# ME_433_Final.net
KiCad netlist of a schematic drawn in EAGLE
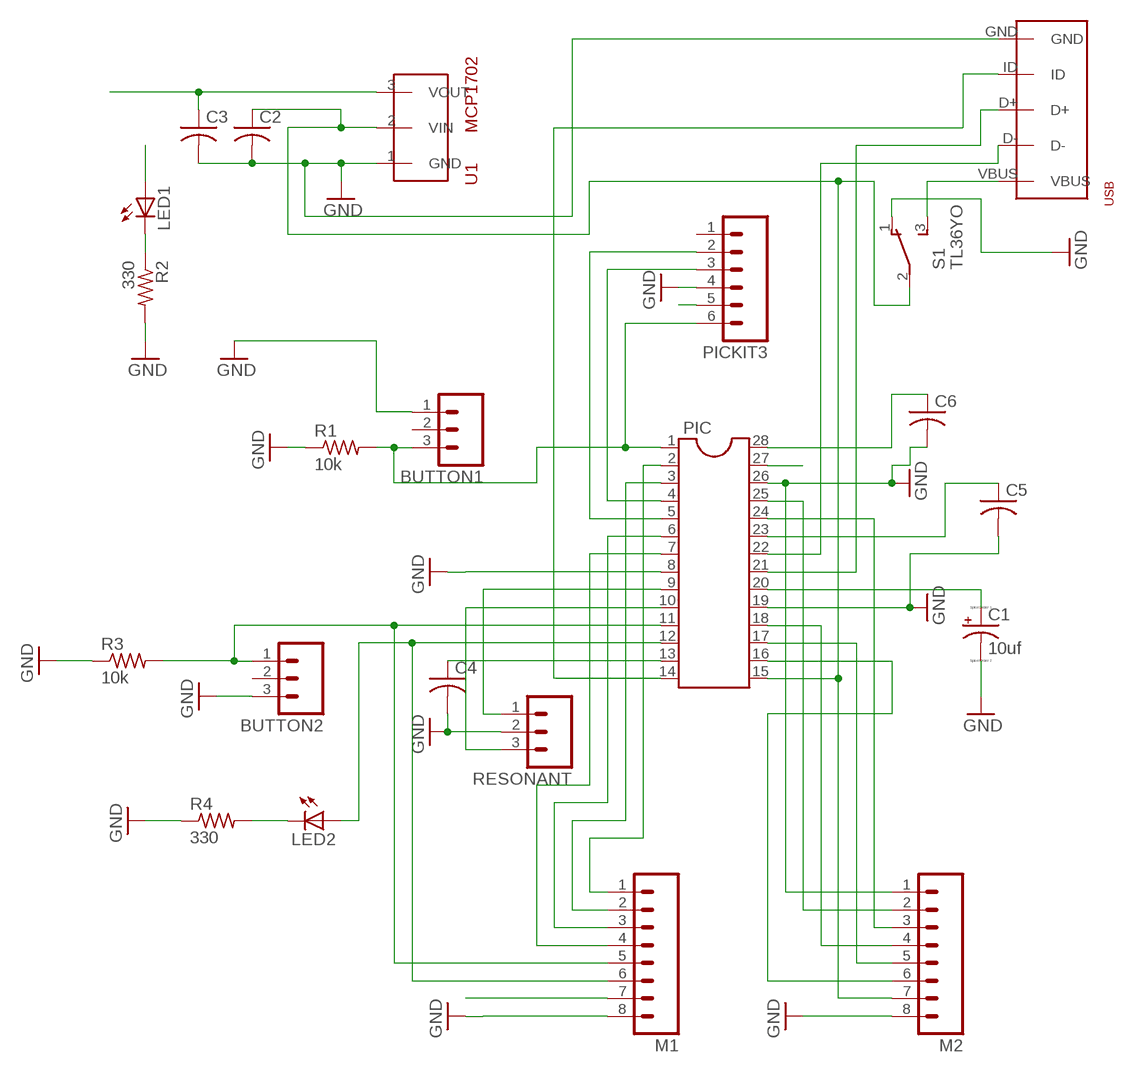
[diagram p0: schematic, sheet 1]

(export (version "E")
  (design (tool "Eeschema 10.0.6"))
  (components
    (comp (ref "BUTTON1")
      (value "M03PTH")
      (footprint "eagle-import:1X03")
      (libsource (lib "eagle-import") (part "M03PTH"))
    )
    (comp (ref "BUTTON2")
      (value "M03PTH")
      (footprint "eagle-import:1X03")
      (libsource (lib "eagle-import") (part "M03PTH"))
    )
    (comp (ref "C1")
      (value "10uf")
      (footprint "eagle-import:E5-10,5")
      (libsource (lib "eagle-import") (part "CPOL-USE5-10.5"))
    )
    (comp (ref "C2")
      (value "C-US025-025X050")
      (footprint "eagle-import:C025-025X050")
      (libsource (lib "eagle-import") (part "C-US025-025X050"))
    )
    (comp (ref "C3")
      (value "C-US025-025X050")
      (footprint "eagle-import:C025-025X050")
      (libsource (lib "eagle-import") (part "C-US025-025X050"))
    )
    (comp (ref "C4")
      (value "C-US025-025X050")
      (footprint "eagle-import:C025-025X050")
      (libsource (lib "eagle-import") (part "C-US025-025X050"))
    )
    (comp (ref "C5")
      (value "C-US025-025X050")
      (footprint "eagle-import:C025-025X050")
      (libsource (lib "eagle-import") (part "C-US025-025X050"))
    )
    (comp (ref "C6")
      (value "C-US025-025X050")
      (footprint "eagle-import:C025-025X050")
      (libsource (lib "eagle-import") (part "C-US025-025X050"))
    )
    (comp (ref "LED1")
      (value "LED3MM")
      (footprint "eagle-import:LED3MM")
      (libsource (lib "eagle-import") (part "LED3MM"))
    )
    (comp (ref "LED2")
      (value "LED3MM")
      (footprint "eagle-import:LED3MM")
      (libsource (lib "eagle-import") (part "LED3MM"))
    )
    (comp (ref "M1")
      (value "M08SILK_FEMALE_PTH")
      (footprint "eagle-import:1X08")
      (libsource (lib "eagle-import") (part "M08SILK_FEMALE_PTH"))
    )
    (comp (ref "M2")
      (value "M08SILK_FEMALE_PTH")
      (footprint "eagle-import:1X08")
      (libsource (lib "eagle-import") (part "M08SILK_FEMALE_PTH"))
    )
    (comp (ref "PIC")
      (value "DIL28-3")
      (footprint "eagle-import:DIL28-3")
      (libsource (lib "eagle-import") (part "DIL28-3"))
    )
    (comp (ref "PICKIT3")
      (value "M06SILK_FEMALE_PTH")
      (footprint "eagle-import:1X06")
      (libsource (lib "eagle-import") (part "M06SILK_FEMALE_PTH"))
    )
    (comp (ref "R1")
      (value "10k")
      (footprint "eagle-import:0309_12")
      (libsource (lib "eagle-import") (part "R-US_0309/12"))
    )
    (comp (ref "R2")
      (value "330")
      (footprint "eagle-import:0309_12")
      (libsource (lib "eagle-import") (part "R-US_0309/12"))
    )
    (comp (ref "R3")
      (value "10k")
      (footprint "eagle-import:0309_12")
      (libsource (lib "eagle-import") (part "R-US_0309/12"))
    )
    (comp (ref "R4")
      (value "330")
      (footprint "eagle-import:0309_12")
      (libsource (lib "eagle-import") (part "R-US_0309/12"))
    )
    (comp (ref "RESONANT")
      (value "M03PTH")
      (footprint "eagle-import:1X03")
      (libsource (lib "eagle-import") (part "M03PTH"))
    )
    (comp (ref "S1")
      (value "TL36YO")
      (footprint "eagle-import:TL3XYO")
      (libsource (lib "eagle-import") (part "TL36YO"))
    )
    (comp (ref "U$1")
      (value "MCP1702TO92")
      (footprint "eagle-import:TO92")
      (libsource (lib "eagle-import") (part "MCP1702TO92"))
    )
    (comp (ref "U$2")
      (value "USB_ME")
      (footprint "eagle-import:USB-MB-H")
      (libsource (lib "eagle-import") (part "USB_ME"))
    )
  )
  (nets
    (net (code "1") (name "/3.3V") (class "Default")
      (node (ref "C3") (pin "1") (pinfunction "1_1") (pintype "passive"))
      (node (ref "C4") (pin "1") (pinfunction "1_1") (pintype "passive"))
      (node (ref "C5") (pin "1") (pinfunction "1_1") (pintype "passive"))
      (node (ref "C6") (pin "1") (pinfunction "1_1") (pintype "passive"))
      (node (ref "LED1") (pin "A") (pinfunction "A_A") (pintype "passive"))
      (node (ref "M1") (pin "7") (pinfunction "7_7") (pintype "passive"))
      (node (ref "PIC") (pin "13") (pinfunction "13_13") (pintype "passive"))
      (node (ref "PIC") (pin "23") (pinfunction "23_23") (pintype "passive"))
      (node (ref "PIC") (pin "28") (pinfunction "28_28") (pintype "passive"))
      (node (ref "PICKIT3") (pin "5") (pinfunction "5_5") (pintype "passive"))
      (node (ref "U$1") (pin "3") (pinfunction "VOUT_3") (pintype "bidirectional"))
    )
    (net (code "2") (name "GND") (class "Default")
      (node (ref "BUTTON1") (pin "1") (pinfunction "1_1") (pintype "passive"))
      (node (ref "BUTTON2") (pin "3") (pinfunction "3_3") (pintype "passive"))
      (node (ref "C1") (pin "-") (pinfunction "-_-") (pintype "passive"))
      (node (ref "C2") (pin "2") (pinfunction "2_2") (pintype "passive"))
      (node (ref "C3") (pin "2") (pinfunction "2_2") (pintype "passive"))
      (node (ref "C4") (pin "2") (pinfunction "2_2") (pintype "passive"))
      (node (ref "C5") (pin "2") (pinfunction "2_2") (pintype "passive"))
      (node (ref "C6") (pin "2") (pinfunction "2_2") (pintype "passive"))
      (node (ref "M1") (pin "8") (pinfunction "8_8") (pintype "passive"))
      (node (ref "M2") (pin "1") (pinfunction "1_1") (pintype "passive"))
      (node (ref "M2") (pin "8") (pinfunction "8_8") (pintype "passive"))
      (node (ref "PIC") (pin "19") (pinfunction "19_19") (pintype "passive"))
      (node (ref "PIC") (pin "26") (pinfunction "26_26") (pintype "passive"))
      (node (ref "PIC") (pin "8") (pinfunction "8_8") (pintype "passive"))
      (node (ref "PICKIT3") (pin "4") (pinfunction "4_4") (pintype "passive"))
      (node (ref "R1") (pin "1") (pinfunction "1_1") (pintype "passive"))
      (node (ref "R2") (pin "2") (pinfunction "2_2") (pintype "passive"))
      (node (ref "R3") (pin "1") (pinfunction "1_1") (pintype "passive"))
      (node (ref "R4") (pin "1") (pinfunction "1_1") (pintype "passive"))
      (node (ref "RESONANT") (pin "2") (pinfunction "2_2") (pintype "passive"))
      (node (ref "S1") (pin "1") (pinfunction "O_1") (pintype "passive"))
      (node (ref "U$1") (pin "1") (pinfunction "GND_1") (pintype "bidirectional"))
      (node (ref "U$2") (pin "GND") (pinfunction "GND_GND") (pintype "bidirectional"))
    )
    (net (code "3") (name "Net-(BUTTON1-Pad3)") (class "Default")
      (node (ref "BUTTON1") (pin "3") (pinfunction "3_3") (pintype "passive"))
      (node (ref "PIC") (pin "1") (pinfunction "1_1") (pintype "passive"))
      (node (ref "PICKIT3") (pin "6") (pinfunction "6_6") (pintype "passive"))
      (node (ref "R1") (pin "2") (pinfunction "2_2") (pintype "passive"))
    )
    (net (code "4") (name "Net-(BUTTON2-Pad1)") (class "Default")
      (node (ref "BUTTON2") (pin "1") (pinfunction "1_1") (pintype "passive"))
      (node (ref "M1") (pin "5") (pinfunction "5_5") (pintype "passive"))
      (node (ref "PIC") (pin "11") (pinfunction "11_11") (pintype "passive"))
      (node (ref "R3") (pin "2") (pinfunction "2_2") (pintype "passive"))
    )
    (net (code "5") (name "Net-(C1-Pad+)") (class "Default")
      (node (ref "C1") (pin "+") (pinfunction "+_+") (pintype "passive"))
      (node (ref "PIC") (pin "20") (pinfunction "20_20") (pintype "passive"))
    )
    (net (code "6") (name "Net-(LED1-C)") (class "Default")
      (node (ref "LED1") (pin "K") (pinfunction "C_K") (pintype "passive"))
      (node (ref "R2") (pin "1") (pinfunction "1_1") (pintype "passive"))
    )
    (net (code "7") (name "Net-(LED2-C)") (class "Default")
      (node (ref "LED2") (pin "K") (pinfunction "C_K") (pintype "passive"))
      (node (ref "R4") (pin "2") (pinfunction "2_2") (pintype "passive"))
    )
    (net (code "8") (name "Net-(LED2-PadA)") (class "Default")
      (node (ref "LED2") (pin "A") (pinfunction "A_A") (pintype "passive"))
      (node (ref "M1") (pin "6") (pinfunction "6_6") (pintype "passive"))
      (node (ref "PIC") (pin "12") (pinfunction "12_12") (pintype "passive"))
    )
    (net (code "9") (name "Net-(M1-Pad1)") (class "Default")
      (node (ref "M1") (pin "1") (pinfunction "1_1") (pintype "passive"))
      (node (ref "PIC") (pin "2") (pinfunction "2_2") (pintype "passive"))
    )
    (net (code "10") (name "Net-(M1-Pad2)") (class "Default")
      (node (ref "M1") (pin "2") (pinfunction "2_2") (pintype "passive"))
      (node (ref "PIC") (pin "3") (pinfunction "3_3") (pintype "passive"))
    )
    (net (code "11") (name "Net-(M1-Pad3)") (class "Default")
      (node (ref "M1") (pin "3") (pinfunction "3_3") (pintype "passive"))
      (node (ref "PIC") (pin "6") (pinfunction "6_6") (pintype "passive"))
    )
    (net (code "12") (name "Net-(M1-Pad4)") (class "Default")
      (node (ref "M1") (pin "4") (pinfunction "4_4") (pintype "passive"))
      (node (ref "PIC") (pin "7") (pinfunction "7_7") (pintype "passive"))
    )
    (net (code "13") (name "Net-(M2-Pad2)") (class "Default")
      (node (ref "M2") (pin "2") (pinfunction "2_2") (pintype "passive"))
      (node (ref "PIC") (pin "25") (pinfunction "25_25") (pintype "passive"))
    )
    (net (code "14") (name "Net-(M2-Pad3)") (class "Default")
      (node (ref "M2") (pin "3") (pinfunction "3_3") (pintype "passive"))
      (node (ref "PIC") (pin "24") (pinfunction "24_24") (pintype "passive"))
    )
    (net (code "15") (name "Net-(M2-Pad4)") (class "Default")
      (node (ref "M2") (pin "4") (pinfunction "4_4") (pintype "passive"))
      (node (ref "PIC") (pin "18") (pinfunction "18_18") (pintype "passive"))
    )
    (net (code "16") (name "Net-(M2-Pad5)") (class "Default")
      (node (ref "M2") (pin "5") (pinfunction "5_5") (pintype "passive"))
      (node (ref "PIC") (pin "17") (pinfunction "17_17") (pintype "passive"))
    )
    (net (code "17") (name "Net-(M2-Pad6)") (class "Default")
      (node (ref "M2") (pin "6") (pinfunction "6_6") (pintype "passive"))
      (node (ref "PIC") (pin "16") (pinfunction "16_16") (pintype "passive"))
    )
    (net (code "18") (name "Net-(PIC-Pad4)") (class "Default")
      (node (ref "PIC") (pin "4") (pinfunction "4_4") (pintype "passive"))
      (node (ref "PICKIT3") (pin "3") (pinfunction "3_3") (pintype "passive"))
    )
    (net (code "19") (name "Net-(PIC-Pad5)") (class "Default")
      (node (ref "PIC") (pin "5") (pinfunction "5_5") (pintype "passive"))
      (node (ref "PICKIT3") (pin "2") (pinfunction "2_2") (pintype "passive"))
    )
    (net (code "20") (name "Net-(PIC-Pad9)") (class "Default")
      (node (ref "PIC") (pin "9") (pinfunction "9_9") (pintype "passive"))
      (node (ref "RESONANT") (pin "1") (pinfunction "1_1") (pintype "passive"))
    )
    (net (code "21") (name "Net-(PIC-Pad10)") (class "Default")
      (node (ref "PIC") (pin "10") (pinfunction "10_10") (pintype "passive"))
      (node (ref "RESONANT") (pin "3") (pinfunction "3_3") (pintype "passive"))
    )
    (net (code "22") (name "Net-(PIC-Pad14)") (class "Default")
      (node (ref "PIC") (pin "14") (pinfunction "14_14") (pintype "passive"))
      (node (ref "U$2") (pin "ID") (pinfunction "ID_ID") (pintype "bidirectional"))
    )
    (net (code "23") (name "Net-(PIC-Pad21)") (class "Default")
      (node (ref "PIC") (pin "21") (pinfunction "21_21") (pintype "passive"))
      (node (ref "U$2") (pin "D+") (pinfunction "D+_D+") (pintype "bidirectional"))
    )
    (net (code "24") (name "Net-(PIC-Pad22)") (class "Default")
      (node (ref "PIC") (pin "22") (pinfunction "22_22") (pintype "passive"))
      (node (ref "U$2") (pin "D-") (pinfunction "D-_D-") (pintype "bidirectional"))
    )
    (net (code "25") (name "Net-(S1-P)") (class "Default")
      (node (ref "C2") (pin "1") (pinfunction "1_1") (pintype "passive"))
      (node (ref "M2") (pin "7") (pinfunction "7_7") (pintype "passive"))
      (node (ref "PIC") (pin "15") (pinfunction "15_15") (pintype "passive"))
      (node (ref "S1") (pin "2") (pinfunction "P_2") (pintype "passive"))
      (node (ref "U$1") (pin "2") (pinfunction "VIN_2") (pintype "bidirectional"))
    )
    (net (code "26") (name "Net-(S1-S)") (class "Default")
      (node (ref "S1") (pin "3") (pinfunction "S_3") (pintype "passive"))
      (node (ref "U$2") (pin "VBUS") (pinfunction "VBUS_VBUS") (pintype "bidirectional"))
    )
    (net (code "27") (name "unconnected-(BUTTON1-Pad2)") (class "Default")
      (node (ref "BUTTON1") (pin "2") (pinfunction "2_2") (pintype "passive"))
    )
    (net (code "28") (name "unconnected-(BUTTON2-Pad2)") (class "Default")
      (node (ref "BUTTON2") (pin "2") (pinfunction "2_2") (pintype "passive"))
    )
    (net (code "29") (name "unconnected-(PIC-Pad27)") (class "Default")
      (node (ref "PIC") (pin "27") (pinfunction "27_27") (pintype "passive"))
    )
    (net (code "30") (name "unconnected-(PICKIT3-Pad1)") (class "Default")
      (node (ref "PICKIT3") (pin "1") (pinfunction "1_1") (pintype "passive"))
    )
  )
)
